# relay_noprotection.net
KiCad netlist of a schematic drawn in Altium Designer
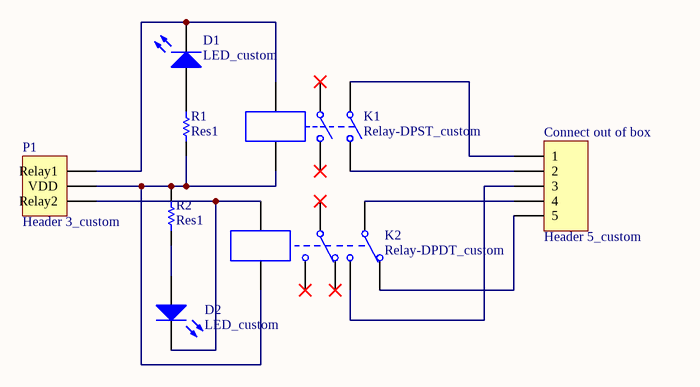
[diagram p0: relay_noprotection.SchDoc]

(export (version "E")
  (design (tool "Eeschema 10.0.6"))
  (components
    (comp (ref "Connect out of box")
      (value "Header 5_custom")
      (footprint "PCB_Footprints:TE5")
      (description "Header, 5-Pin")
      (fields (field (name "PUBLISHER") "Altium Limited"))
      (libsource (lib "Integrated_Library_1") (part "Header 5_custom"))
    )
    (comp (ref "D1")
      (value "LED_custom")
      (footprint "PCB_Footprints:LED_Custom")
      (description "Typical INFRARED GaAs LED")
      (fields (field (name "PUBLISHER") "Altium Limited"))
      (libsource (lib "Integrated_Library_1") (part "LED_custom"))
    )
    (comp (ref "D2")
      (value "LED_custom")
      (footprint "PCB_Footprints:LED_Custom")
      (description "Typical INFRARED GaAs LED")
      (fields (field (name "PUBLISHER") "Altium Limited"))
      (libsource (lib "Integrated_Library_1") (part "LED_custom"))
    )
    (comp (ref "K1")
      (value "Relay-DPST_custom")
      (footprint "Relay-DPST_custom")
      (description "Dual-Pole Single-Throw Relay")
      (fields (field (name "PUBLISHER") "Altium Limited"))
      (libsource (lib "Integrated_Library_1") (part "Relay-DPST_custom"))
    )
    (comp (ref "K2")
      (value "Relay-DPDT_custom")
      (footprint "Relay-DPDT_custom")
      (description "Dual-Pole Dual-Throw Relay")
      (fields (field (name "PUBLISHER") "Altium Limited"))
      (libsource (lib "Integrated_Library_1") (part "Relay-DPDT_custom"))
    )
    (comp (ref "P1")
      (value "Header 3_custom")
      (footprint "PCB_Footprints:TB3")
      (description "Header, 3-Pin")
      (fields (field (name "PUBLISHER") "Altium Limited"))
      (libsource (lib "Integrated_Library_1") (part "Header 3_custom"))
    )
    (comp (ref "R1")
      (value "Res1")
      (footprint "AXIAL-0.3")
      (description "Resistor")
      (fields (field (name "PUBLISHER") "Altium Limited"))
      (libsource (lib "Miscellaneous Devices") (part "Res1"))
    )
    (comp (ref "R2")
      (value "Res1")
      (footprint "AXIAL-0.3")
      (description "Resistor")
      (fields (field (name "PUBLISHER") "Altium Limited"))
      (libsource (lib "Miscellaneous Devices") (part "Res1"))
    )
  )
  (nets
    (net (code "1") (name "Net-(Connect out of box-Pad1)") (class "Default")
      (node (ref "Connect out of box") (pin "1") (pinfunction "1_1") (pintype "passive"))
      (node (ref "K1") (pin "1") (pinfunction "1_1") (pintype "passive"))
    )
    (net (code "2") (name "Net-(Connect out of box-Pad2)") (class "Default")
      (node (ref "Connect out of box") (pin "2") (pinfunction "2_2") (pintype "passive"))
      (node (ref "K1") (pin "2") (pinfunction "2_2") (pintype "passive"))
    )
    (net (code "3") (name "Net-(Connect out of box-Pad3)") (class "Default")
      (node (ref "Connect out of box") (pin "3") (pinfunction "3_3") (pintype "passive"))
      (node (ref "K2") (pin "3") (pinfunction "3_3") (pintype "passive"))
    )
    (net (code "4") (name "Net-(Connect out of box-Pad4)") (class "Default")
      (node (ref "Connect out of box") (pin "4") (pinfunction "4_4") (pintype "passive"))
      (node (ref "K2") (pin "1") (pinfunction "1_1") (pintype "passive"))
    )
    (net (code "5") (name "Net-(Connect out of box-Pad5)") (class "Default")
      (node (ref "Connect out of box") (pin "5") (pinfunction "5_5") (pintype "passive"))
      (node (ref "K2") (pin "2") (pinfunction "2_2") (pintype "passive"))
    )
    (net (code "6") (name "Net-(D1-A)") (class "Default")
      (node (ref "D1") (pin "1") (pinfunction "A_1") (pintype "passive"))
      (node (ref "R1") (pin "2") (pinfunction "2_2") (pintype "passive"))
    )
    (net (code "7") (name "Net-(D1-K)") (class "Default")
      (node (ref "D1") (pin "2") (pinfunction "K_2") (pintype "passive"))
      (node (ref "K1") (pin "5") (pinfunction "5_5") (pintype "passive"))
      (node (ref "P1") (pin "3") (pinfunction "Relay1_3") (pintype "passive"))
    )
    (net (code "8") (name "Net-(D2-A)") (class "Default")
      (node (ref "D2") (pin "1") (pinfunction "A_1") (pintype "passive"))
      (node (ref "R2") (pin "2") (pinfunction "2_2") (pintype "passive"))
    )
    (net (code "9") (name "Net-(D2-K)") (class "Default")
      (node (ref "D2") (pin "2") (pinfunction "K_2") (pintype "passive"))
      (node (ref "K2") (pin "7") (pinfunction "7_7") (pintype "passive"))
      (node (ref "P1") (pin "1") (pinfunction "Relay2_1") (pintype "passive"))
    )
    (net (code "10") (name "Net-(P1-VDD)") (class "Default")
      (node (ref "K1") (pin "6") (pinfunction "6_6") (pintype "passive"))
      (node (ref "K2") (pin "8") (pinfunction "8_8") (pintype "passive"))
      (node (ref "P1") (pin "2") (pinfunction "VDD_2") (pintype "passive"))
      (node (ref "R1") (pin "1") (pinfunction "1_1") (pintype "passive"))
      (node (ref "R2") (pin "1") (pinfunction "1_1") (pintype "passive"))
    )
    (net (code "11") (name "unconnected-(K1-Pad3)") (class "Default")
      (node (ref "K1") (pin "3") (pinfunction "3_3") (pintype "passive+no_connect"))
    )
    (net (code "12") (name "unconnected-(K1-Pad4)") (class "Default")
      (node (ref "K1") (pin "4") (pinfunction "4_4") (pintype "passive+no_connect"))
    )
    (net (code "13") (name "unconnected-(K2-Pad4)") (class "Default")
      (node (ref "K2") (pin "4") (pinfunction "4_4") (pintype "passive+no_connect"))
    )
    (net (code "14") (name "unconnected-(K2-Pad5)") (class "Default")
      (node (ref "K2") (pin "5") (pinfunction "5_5") (pintype "passive+no_connect"))
    )
    (net (code "15") (name "unconnected-(K2-Pad6)") (class "Default")
      (node (ref "K2") (pin "6") (pinfunction "6_6") (pintype "passive+no_connect"))
    )
  )
)
